# Rear_brake_lamp_v1.net
KiCad netlist of a schematic drawn in EAGLE
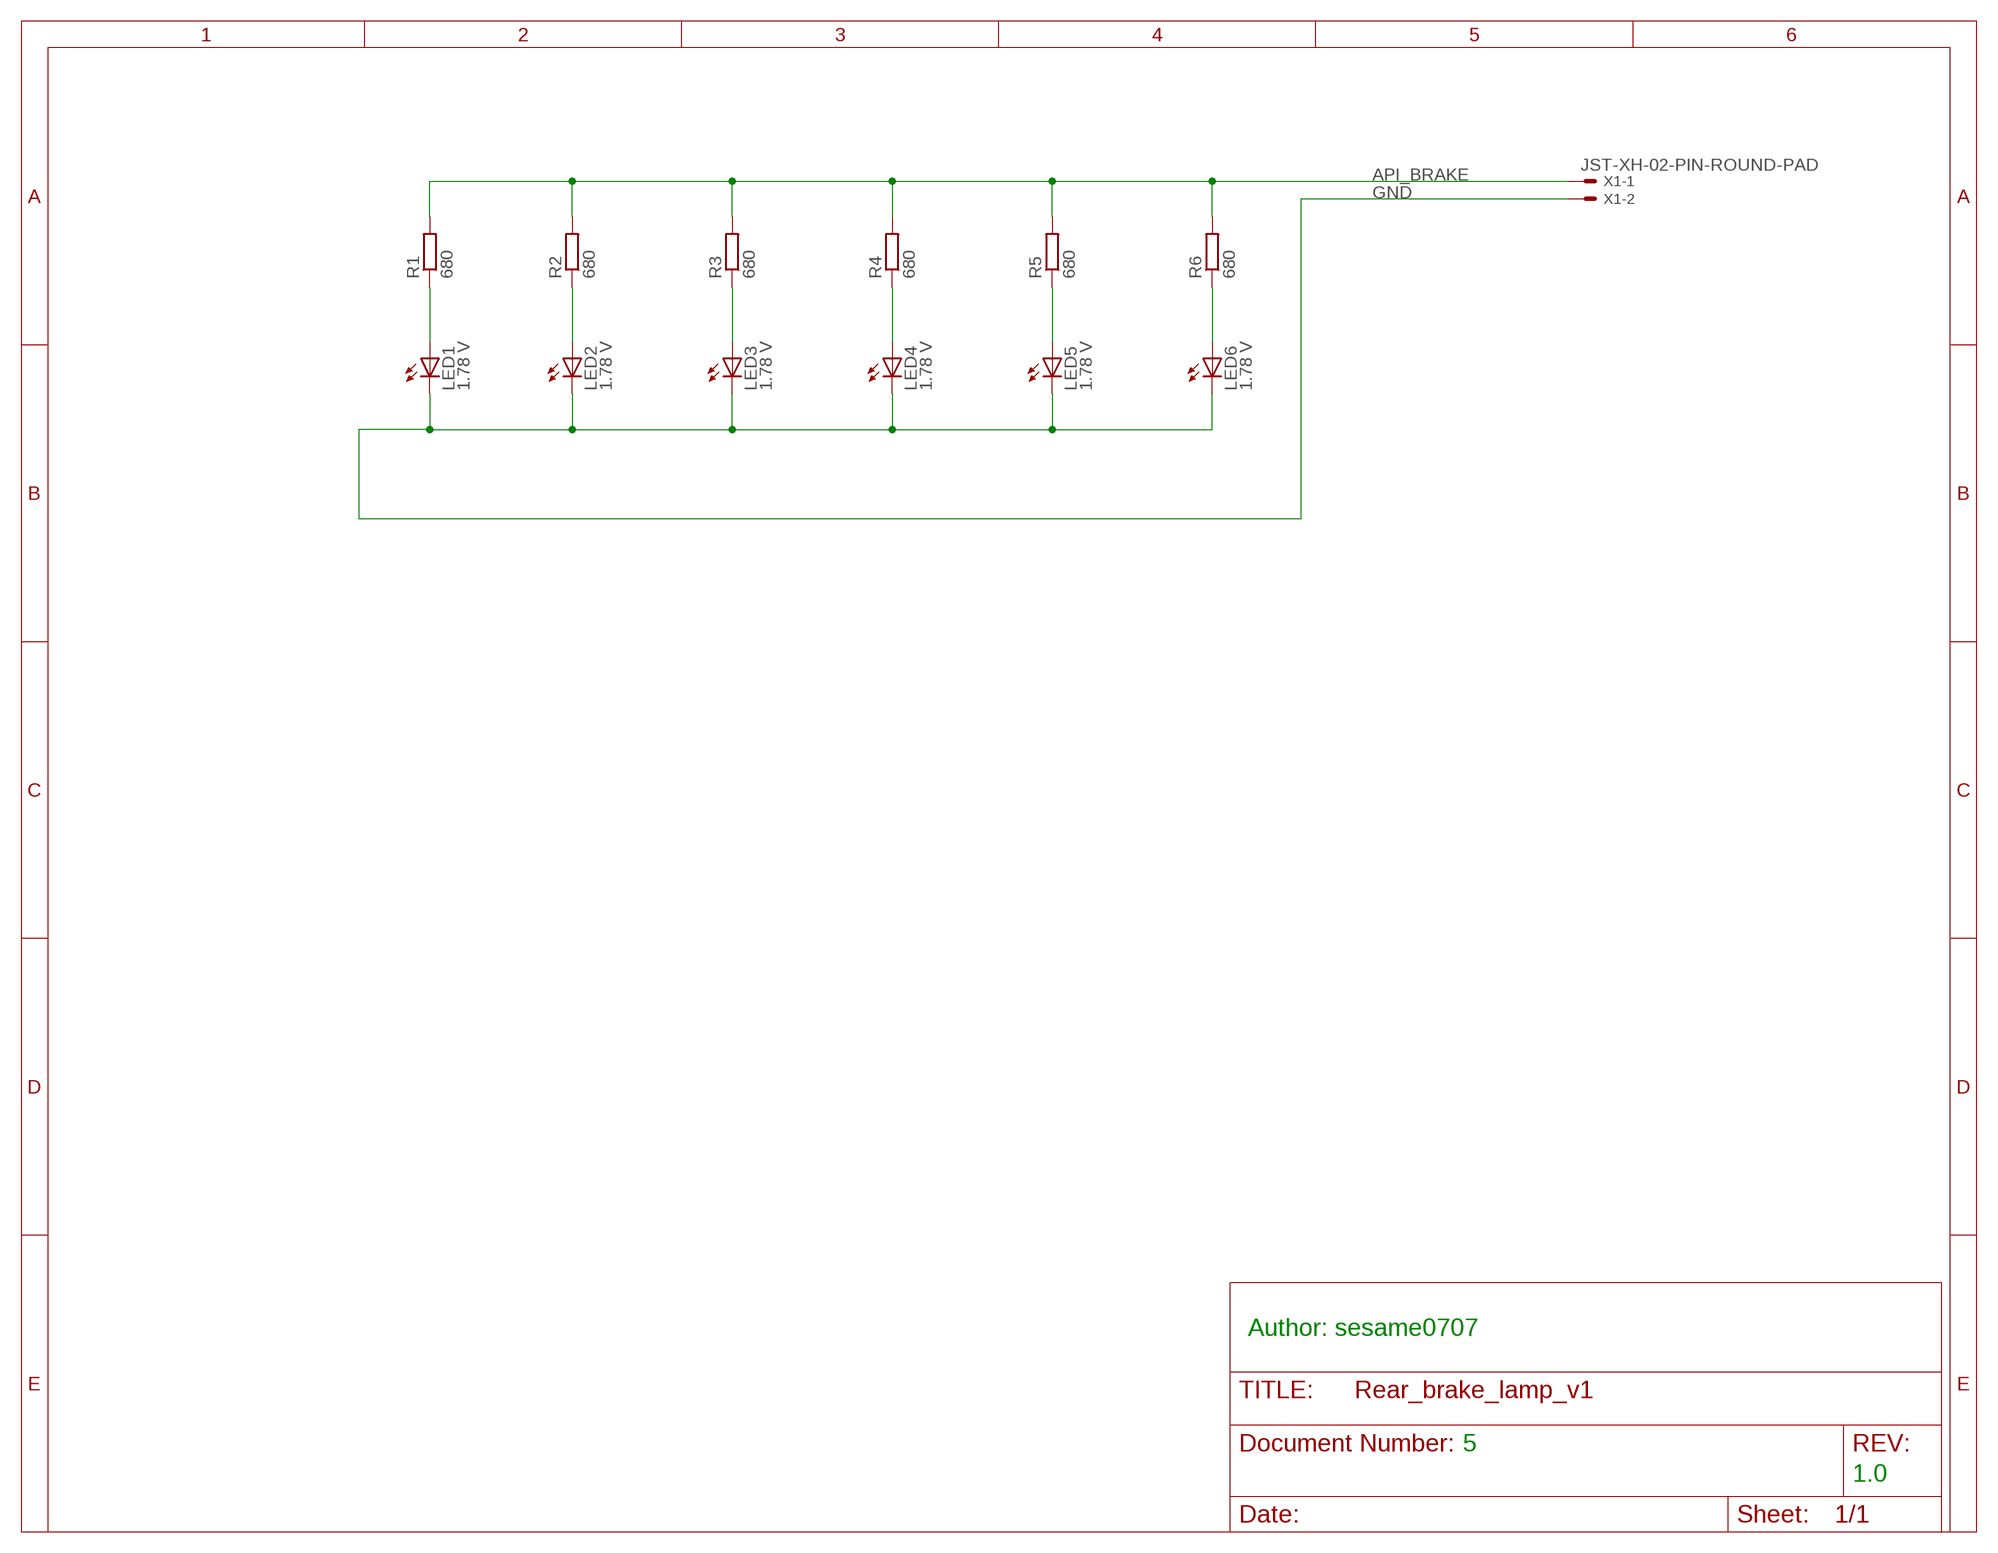
[diagram p0: schematic, sheet 1]

(export (version "E")
  (design (tool "Eeschema 10.0.6"))
  (components
    (comp (ref "LED1")
      (value "1.78 V")
      (footprint "eagle-import:LED5MM")
      (libsource (lib "eagle-import") (part "LED5MM"))
    )
    (comp (ref "LED2")
      (value "1.78 V")
      (footprint "eagle-import:LED5MM")
      (libsource (lib "eagle-import") (part "LED5MM"))
    )
    (comp (ref "LED3")
      (value "1.78 V")
      (footprint "eagle-import:LED5MM")
      (libsource (lib "eagle-import") (part "LED5MM"))
    )
    (comp (ref "LED4")
      (value "1.78 V")
      (footprint "eagle-import:LED5MM")
      (libsource (lib "eagle-import") (part "LED5MM"))
    )
    (comp (ref "LED5")
      (value "1.78 V")
      (footprint "eagle-import:LED5MM")
      (libsource (lib "eagle-import") (part "LED5MM"))
    )
    (comp (ref "LED6")
      (value "1.78 V")
      (footprint "eagle-import:LED5MM")
      (libsource (lib "eagle-import") (part "LED5MM"))
    )
    (comp (ref "R1")
      (value "680")
      (footprint "eagle-import:0204V")
      (libsource (lib "eagle-import") (part "R-EU_0204/2V"))
    )
    (comp (ref "R2")
      (value "680")
      (footprint "eagle-import:0204V")
      (libsource (lib "eagle-import") (part "R-EU_0204/2V"))
    )
    (comp (ref "R3")
      (value "680")
      (footprint "eagle-import:0204V")
      (libsource (lib "eagle-import") (part "R-EU_0204/2V"))
    )
    (comp (ref "R4")
      (value "680")
      (footprint "eagle-import:0204V")
      (libsource (lib "eagle-import") (part "R-EU_0204/2V"))
    )
    (comp (ref "R5")
      (value "680")
      (footprint "eagle-import:0204V")
      (libsource (lib "eagle-import") (part "R-EU_0204/2V"))
    )
    (comp (ref "R6")
      (value "680")
      (footprint "eagle-import:0204V")
      (libsource (lib "eagle-import") (part "R-EU_0204/2V"))
    )
    (comp (ref "X1")
      (value "JST-XH-02-PIN-ROUND-PAD")
      (footprint "eagle-import:JST-XH-02-PACKAGE-ROUND-PAD")
      (libsource (lib "eagle-import") (part "JST-XH-02-PIN-ROUND-PAD"))
    )
  )
  (nets
    (net (code "1") (name "/API_BRAKE") (class "Default")
      (node (ref "R1") (pin "2") (pinfunction "2_2") (pintype "passive"))
      (node (ref "R2") (pin "2") (pinfunction "2_2") (pintype "passive"))
      (node (ref "R3") (pin "2") (pinfunction "2_2") (pintype "passive"))
      (node (ref "R4") (pin "2") (pinfunction "2_2") (pintype "passive"))
      (node (ref "R5") (pin "2") (pinfunction "2_2") (pintype "passive"))
      (node (ref "R6") (pin "2") (pinfunction "2_2") (pintype "passive"))
      (node (ref "X1") (pin "1") (pinfunction "S_1") (pintype "passive"))
    )
    (net (code "2") (name "/GND") (class "Default")
      (node (ref "LED1") (pin "K") (pinfunction "C_K") (pintype "passive"))
      (node (ref "LED2") (pin "K") (pinfunction "C_K") (pintype "passive"))
      (node (ref "LED3") (pin "K") (pinfunction "C_K") (pintype "passive"))
      (node (ref "LED4") (pin "K") (pinfunction "C_K") (pintype "passive"))
      (node (ref "LED5") (pin "K") (pinfunction "C_K") (pintype "passive"))
      (node (ref "LED6") (pin "K") (pinfunction "C_K") (pintype "passive"))
      (node (ref "X1") (pin "2") (pinfunction "S_2") (pintype "passive"))
    )
    (net (code "3") (name "Net-(LED1-PadA)") (class "Default")
      (node (ref "LED1") (pin "A") (pinfunction "A_A") (pintype "passive"))
      (node (ref "R1") (pin "1") (pinfunction "1_1") (pintype "passive"))
    )
    (net (code "4") (name "Net-(LED2-PadA)") (class "Default")
      (node (ref "LED2") (pin "A") (pinfunction "A_A") (pintype "passive"))
      (node (ref "R2") (pin "1") (pinfunction "1_1") (pintype "passive"))
    )
    (net (code "5") (name "Net-(LED3-PadA)") (class "Default")
      (node (ref "LED3") (pin "A") (pinfunction "A_A") (pintype "passive"))
      (node (ref "R3") (pin "1") (pinfunction "1_1") (pintype "passive"))
    )
    (net (code "6") (name "Net-(LED4-PadA)") (class "Default")
      (node (ref "LED4") (pin "A") (pinfunction "A_A") (pintype "passive"))
      (node (ref "R4") (pin "1") (pinfunction "1_1") (pintype "passive"))
    )
    (net (code "7") (name "Net-(LED5-PadA)") (class "Default")
      (node (ref "LED5") (pin "A") (pinfunction "A_A") (pintype "passive"))
      (node (ref "R5") (pin "1") (pinfunction "1_1") (pintype "passive"))
    )
    (net (code "8") (name "Net-(LED6-PadA)") (class "Default")
      (node (ref "LED6") (pin "A") (pinfunction "A_A") (pintype "passive"))
      (node (ref "R6") (pin "1") (pinfunction "1_1") (pintype "passive"))
    )
  )
)
